# Digital_Final_-_BlackChat.net
KiCad netlist of a schematic drawn in Altium Designer
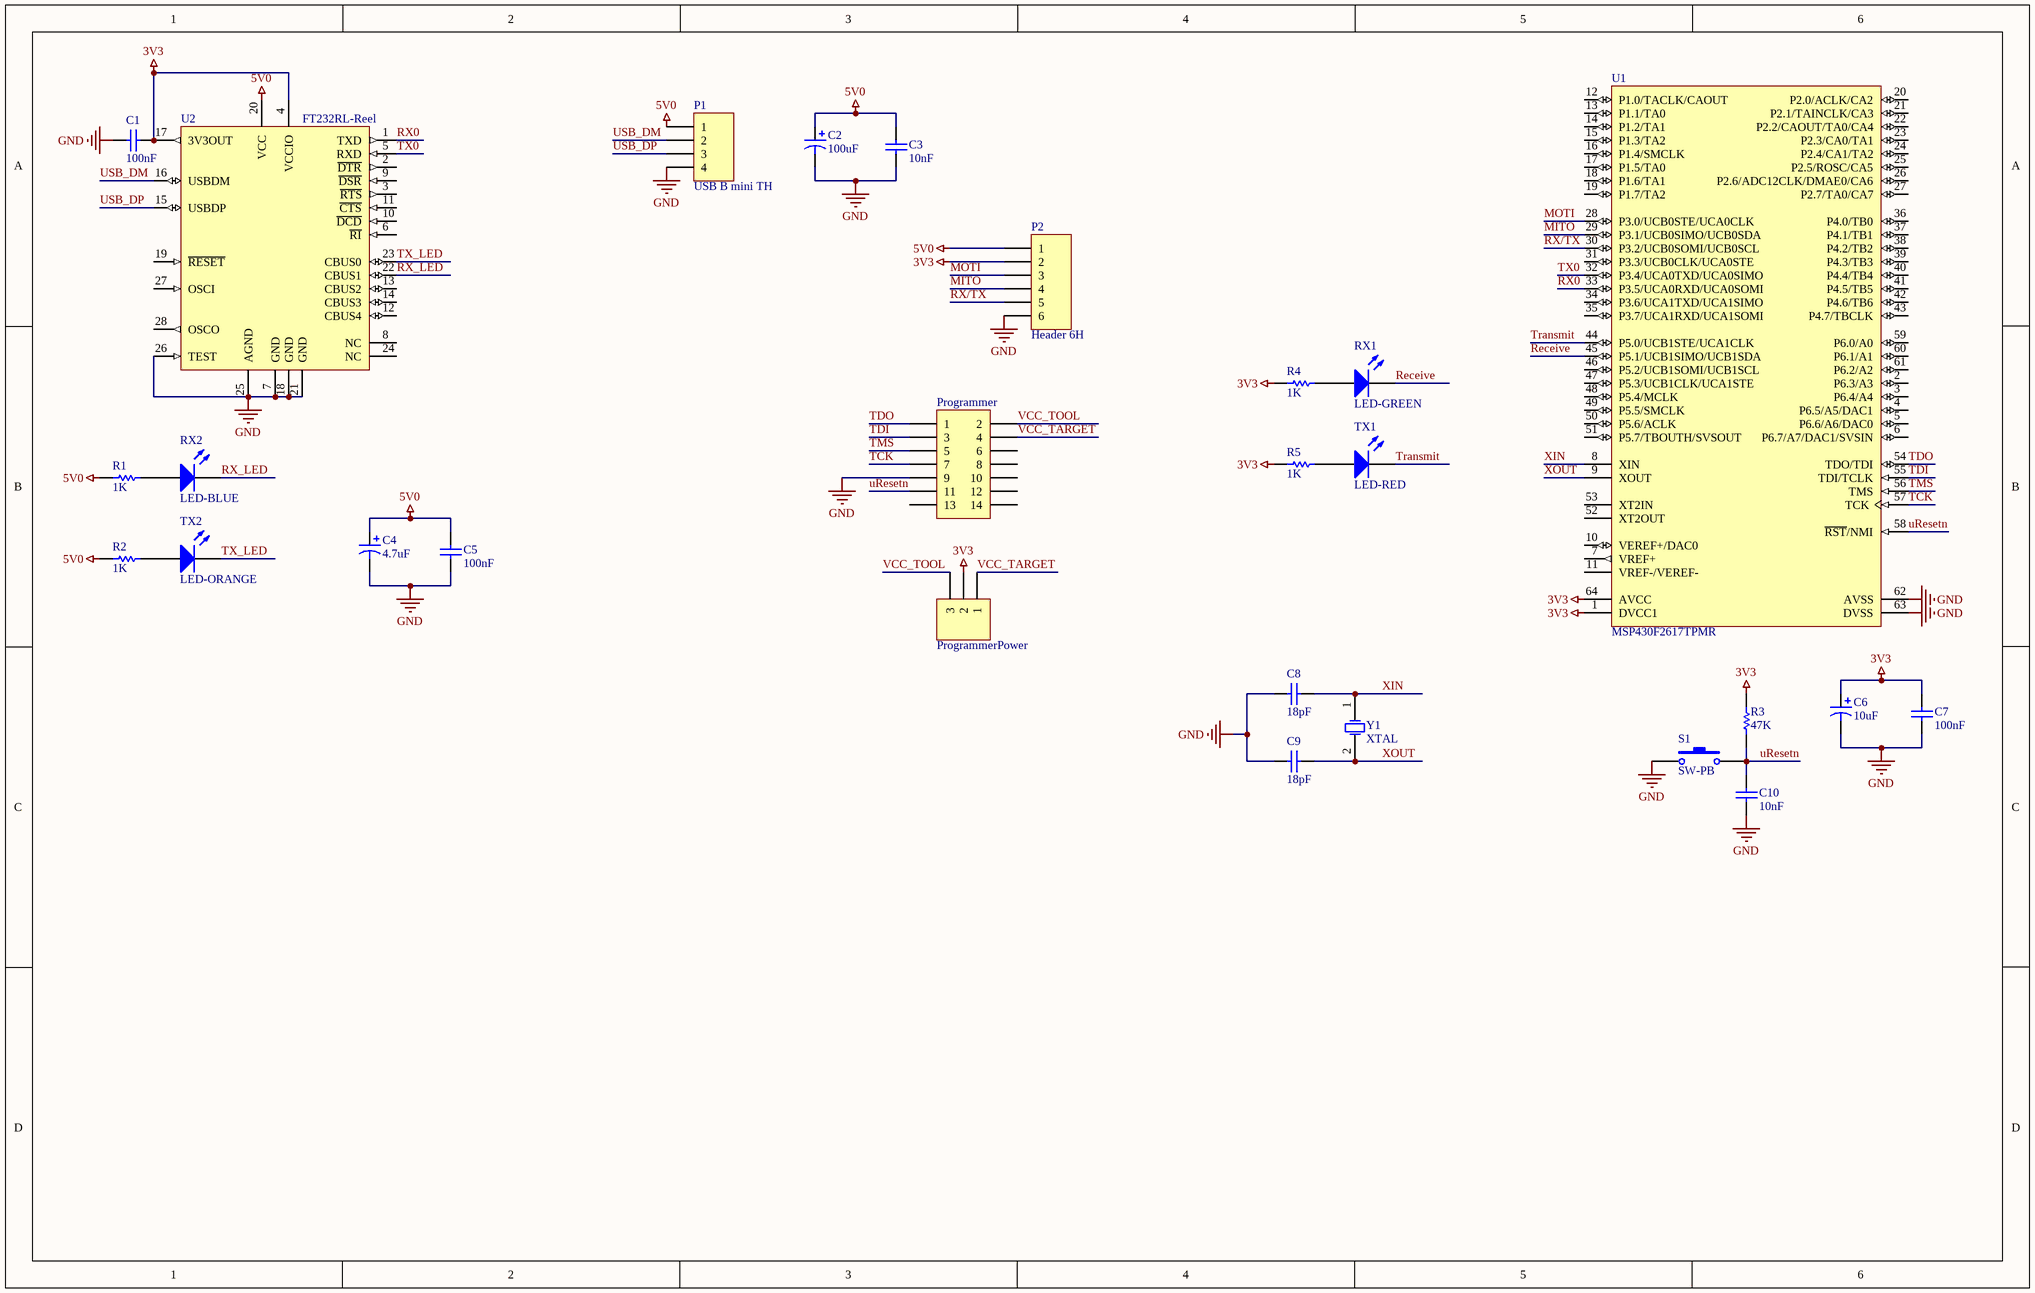
[diagram p0: Digital Final - BlackChat.SchDoc]

(export (version "E")
  (design (tool "Eeschema 10.0.6"))
  (components
    (comp (ref "C1")
      (value "100nF")
      (footprint "CAP-0805")
      (description "Capacitor")
      (fields (field (name "Comment") "Cap") (field (name "PUBLISHER") "Altium Limited"))
      (libsource (lib "Miscellaneous Devices") (part "Cap"))
    )
    (comp (ref "C2")
      (value "100uF")
      (footprint "CAP-0805")
      (description "Polarized Capacitor (Surface Mount)")
      (fields (field (name "Comment") "Cap Pol3") (field (name "PUBLISHER") "Altium Limited"))
      (libsource (lib "Miscellaneous Devices") (part "Cap Pol3"))
    )
    (comp (ref "C3")
      (value "10nF")
      (footprint "CAP-0805")
      (description "Capacitor")
      (fields (field (name "Comment") "Cap") (field (name "PUBLISHER") "Altium Limited"))
      (libsource (lib "Miscellaneous Devices") (part "Cap"))
    )
    (comp (ref "C4")
      (value "4.7uF")
      (footprint "CAP-0805")
      (description "Polarized Capacitor (Surface Mount)")
      (fields (field (name "Comment") "Cap Pol3") (field (name "PUBLISHER") "Altium Limited"))
      (libsource (lib "Miscellaneous Devices") (part "Cap Pol3"))
    )
    (comp (ref "C5")
      (value "100nF")
      (footprint "CAP-0805")
      (description "Capacitor")
      (fields (field (name "Comment") "Cap") (field (name "PUBLISHER") "Altium Limited"))
      (libsource (lib "Miscellaneous Devices") (part "Cap"))
    )
    (comp (ref "C6")
      (value "10uF")
      (footprint "CAP-0805")
      (description "Polarized Capacitor (Surface Mount)")
      (fields (field (name "Comment") "Cap Pol3") (field (name "PUBLISHER") "Altium Limited"))
      (libsource (lib "Miscellaneous Devices") (part "Cap Pol3"))
    )
    (comp (ref "C7")
      (value "100nF")
      (footprint "CAP-0805")
      (description "Capacitor")
      (fields (field (name "Comment") "Cap") (field (name "PUBLISHER") "Altium Limited"))
      (libsource (lib "Miscellaneous Devices") (part "Cap"))
    )
    (comp (ref "C8")
      (value "18pF")
      (footprint "CAP-0805")
      (description "Capacitor")
      (fields (field (name "Comment") "Cap") (field (name "PUBLISHER") "Altium Limited"))
      (libsource (lib "Miscellaneous Devices") (part "Cap"))
    )
    (comp (ref "C9")
      (value "18pF")
      (footprint "CAP-0805")
      (description "Capacitor")
      (fields (field (name "Comment") "Cap") (field (name "PUBLISHER") "Altium Limited"))
      (libsource (lib "Miscellaneous Devices") (part "Cap"))
    )
    (comp (ref "C10")
      (value "10nF")
      (footprint "CAP-0805")
      (description "Capacitor")
      (fields (field (name "Comment") "Cap") (field (name "PUBLISHER") "Altium Limited"))
      (libsource (lib "Miscellaneous Devices") (part "Cap"))
    )
    (comp (ref "P1")
      (value "USB B mini TH")
      (footprint "USB B mini Molex")
      (fields (field (name "PUBLISHER") "Altium Limited"))
      (libsource (lib "ECE Lib") (part "USB B mini TH"))
    )
    (comp (ref "P2")
      (value "Header 6H")
      (footprint "HDR1X6H")
      (description "Header, 6-Pin, Right Angle")
      (fields (field (name "PUBLISHER") "Altium Limited"))
      (libsource (lib "Miscellaneous Connectors") (part "Header 6H"))
    )
    (comp (ref "Programmer")
      (value "Header 7X2")
      (footprint "HDR2X7")
      (description "Header, 7-Pin, Dual row")
      (fields (field (name "PUBLISHER") "Altium Limited"))
      (libsource (lib "Miscellaneous Connectors") (part "Header 7X2"))
    )
    (comp (ref "ProgrammerPower")
      (value "Header 3")
      (footprint "HDR1X3")
      (description "Header, 3-Pin")
      (fields (field (name "PUBLISHER") "Altium Limited"))
      (libsource (lib "Miscellaneous Connectors") (part "Header 3"))
    )
    (comp (ref "R1")
      (value "1K")
      (footprint "RES-0805")
      (description "Resistor")
      (fields (field (name "Comment") "Res1") (field (name "PUBLISHER") "Altium Limited"))
      (libsource (lib "Miscellaneous Devices") (part "Res1"))
    )
    (comp (ref "R2")
      (value "1K")
      (footprint "RES-0805")
      (description "Resistor")
      (fields (field (name "Comment") "Res1") (field (name "PUBLISHER") "Altium Limited"))
      (libsource (lib "Miscellaneous Devices") (part "Res1"))
    )
    (comp (ref "R3")
      (value "47K")
      (footprint "RES-0805")
      (description "Resistor")
      (fields (field (name "Comment") "Res1") (field (name "PUBLISHER") "Altium Limited"))
      (libsource (lib "Miscellaneous Devices") (part "Res1"))
    )
    (comp (ref "R4")
      (value "1K")
      (footprint "RES-0805")
      (description "Resistor")
      (fields (field (name "Comment") "Res1") (field (name "PUBLISHER") "Altium Limited"))
      (libsource (lib "Miscellaneous Devices") (part "Res1"))
    )
    (comp (ref "R5")
      (value "1K")
      (footprint "RES-0805")
      (description "Resistor")
      (fields (field (name "Comment") "Res1") (field (name "PUBLISHER") "Altium Limited"))
      (libsource (lib "Miscellaneous Devices") (part "Res1"))
    )
    (comp (ref "RX1")
      (value "LED-GREEN")
      (footprint "LED-0805")
      (description "Light Emitting Diode")
      (libsource (lib "BlackChat Library") (part "LED-GENERIC"))
    )
    (comp (ref "RX2")
      (value "LED-BLUE")
      (footprint "LED-0805")
      (description "Light Emitting Diode")
      (libsource (lib "BlackChat Library") (part "LED-GENERIC"))
    )
    (comp (ref "S1")
      (value "SW-PB")
      (footprint "SW PB")
      (description "DIGIKEY SW400-ND")
      (fields (field (name "PUBLISHER") "Altium Limited"))
      (libsource (lib "ECE Lib") (part "SW-PB"))
    )
    (comp (ref "TX1")
      (value "LED-RED")
      (footprint "LED-0805")
      (description "Light Emitting Diode")
      (libsource (lib "BlackChat Library") (part "LED-GENERIC"))
    )
    (comp (ref "TX2")
      (value "LED-ORANGE")
      (footprint "LED-0805")
      (description "Light Emitting Diode")
      (libsource (lib "BlackChat Library") (part "LED-GENERIC"))
    )
    (comp (ref "U1")
      (value "MSP430F2617TPMR")
      (footprint "TI-PM64_N")
      (fields (field (name "MANUFACTURER") "Texas Instruments"))
      (libsource (lib "TI Microcontroller MSP430 16-bit Ultra-Low Power") (part "MSP430F2617TPMR"))
    )
    (comp (ref "U2")
      (value "FT232RL-Reel")
      (footprint "SSOP-28_N")
      (description "USB UART Asynchronous Serial Data Transfer Chip, SSOP-28, Tape and Reel")
      (fields (field (name "PUBLISHER") "Altium Limited"))
      (libsource (lib "BlackChat Library") (part "FT232RL-Reel"))
    )
    (comp (ref "Y1")
      (value "XTAL")
      (footprint "R38")
      (description "Crystal Oscillator")
      (fields (field (name "PUBLISHER") "Altium Limited"))
      (libsource (lib "Miscellaneous Devices") (part "XTAL"))
    )
  )
  (nets
    (net (code "1") (name "/MITO") (class "Default")
      (node (ref "P2") (pin "4") (pinfunction "4_4") (pintype "passive"))
      (node (ref "U1") (pin "29") (pinfunction "P3.1/UCB0SIMO/UCB0SDA_29") (pintype "bidirectional"))
    )
    (net (code "2") (name "/MOTI") (class "Default")
      (node (ref "P2") (pin "3") (pinfunction "3_3") (pintype "passive"))
      (node (ref "U1") (pin "28") (pinfunction "P3.0/UCB0STE/UCA0CLK_28") (pintype "bidirectional"))
    )
    (net (code "3") (name "/RX0") (class "Default")
      (node (ref "U1") (pin "33") (pinfunction "P3.5/UCA0RXD/UCA0SOMI_33") (pintype "bidirectional"))
      (node (ref "U2") (pin "1") (pinfunction "TXD_1") (pintype "output"))
    )
    (net (code "4") (name "/RX_LED") (class "Default")
      (node (ref "RX2") (pin "2") (pinfunction "K_2") (pintype "passive"))
      (node (ref "U2") (pin "22") (pinfunction "CBUS1_22") (pintype "bidirectional"))
    )
    (net (code "5") (name "/RX{slash}~{TX}") (class "Default")
      (node (ref "P2") (pin "5") (pinfunction "5_5") (pintype "passive"))
      (node (ref "U1") (pin "30") (pinfunction "P3.2/UCB0SOMI/UCB0SCL_30") (pintype "bidirectional"))
    )
    (net (code "6") (name "/Receive") (class "Default")
      (node (ref "RX1") (pin "2") (pinfunction "K_2") (pintype "passive"))
      (node (ref "U1") (pin "45") (pinfunction "P5.1/UCB1SIMO/UCB1SDA_45") (pintype "bidirectional"))
    )
    (net (code "7") (name "/TCK") (class "Default")
      (node (ref "Programmer") (pin "7") (pinfunction "7_7") (pintype "passive"))
      (node (ref "U1") (pin "57") (pinfunction "TCK_57") (pintype "input"))
    )
    (net (code "8") (name "/TDI") (class "Default")
      (node (ref "Programmer") (pin "3") (pinfunction "3_3") (pintype "passive"))
      (node (ref "U1") (pin "55") (pinfunction "TDI/TCLK_55") (pintype "input"))
    )
    (net (code "9") (name "/TDO") (class "Default")
      (node (ref "Programmer") (pin "1") (pinfunction "1_1") (pintype "passive"))
      (node (ref "U1") (pin "54") (pinfunction "TDO/TDI_54") (pintype "bidirectional"))
    )
    (net (code "10") (name "/TMS") (class "Default")
      (node (ref "Programmer") (pin "5") (pinfunction "5_5") (pintype "passive"))
      (node (ref "U1") (pin "56") (pinfunction "TMS_56") (pintype "input"))
    )
    (net (code "11") (name "/TX0") (class "Default")
      (node (ref "U1") (pin "32") (pinfunction "P3.4/UCA0TXD/UCA0SIMO_32") (pintype "bidirectional"))
      (node (ref "U2") (pin "5") (pinfunction "RXD_5") (pintype "input"))
    )
    (net (code "12") (name "/TX_LED") (class "Default")
      (node (ref "TX2") (pin "2") (pinfunction "K_2") (pintype "passive"))
      (node (ref "U2") (pin "23") (pinfunction "CBUS0_23") (pintype "bidirectional"))
    )
    (net (code "13") (name "/Transmit") (class "Default")
      (node (ref "TX1") (pin "2") (pinfunction "K_2") (pintype "passive"))
      (node (ref "U1") (pin "44") (pinfunction "P5.0/UCB1STE/UCA1CLK_44") (pintype "bidirectional"))
    )
    (net (code "14") (name "/USB_DM") (class "Default")
      (node (ref "P1") (pin "2") (pinfunction "2_2") (pintype "passive"))
      (node (ref "U2") (pin "16") (pinfunction "USBDM_16") (pintype "bidirectional"))
    )
    (net (code "15") (name "/USB_DP") (class "Default")
      (node (ref "P1") (pin "3") (pinfunction "3_3") (pintype "passive"))
      (node (ref "U2") (pin "15") (pinfunction "USBDP_15") (pintype "bidirectional"))
    )
    (net (code "16") (name "/VCC_TARGET") (class "Default")
      (node (ref "Programmer") (pin "4") (pinfunction "4_4") (pintype "passive"))
      (node (ref "ProgrammerPower") (pin "1") (pinfunction "1_1") (pintype "passive"))
    )
    (net (code "17") (name "/VCC_TOOL") (class "Default")
      (node (ref "Programmer") (pin "2") (pinfunction "2_2") (pintype "passive"))
      (node (ref "ProgrammerPower") (pin "3") (pinfunction "3_3") (pintype "passive"))
    )
    (net (code "18") (name "/XIN") (class "Default")
      (node (ref "C8") (pin "1") (pinfunction "1_1") (pintype "passive"))
      (node (ref "U1") (pin "8") (pinfunction "XIN_8") (pintype "passive"))
      (node (ref "Y1") (pin "1") (pinfunction "OSC1_1") (pintype "passive"))
    )
    (net (code "19") (name "/XOUT") (class "Default")
      (node (ref "C9") (pin "1") (pinfunction "1_1") (pintype "passive"))
      (node (ref "U1") (pin "9") (pinfunction "XOUT_9") (pintype "passive"))
      (node (ref "Y1") (pin "2") (pinfunction "OSC2_2") (pintype "passive"))
    )
    (net (code "20") (name "/uResetn") (class "Default")
      (node (ref "C10") (pin "2") (pinfunction "2_2") (pintype "passive"))
      (node (ref "Programmer") (pin "11") (pinfunction "11_11") (pintype "passive"))
      (node (ref "R3") (pin "1") (pinfunction "1_1") (pintype "passive"))
      (node (ref "S1") (pin "2") (pinfunction "2_2") (pintype "passive"))
      (node (ref "U1") (pin "58") (pinfunction "~{RST}/NMI_58") (pintype "input"))
    )
    (net (code "21") (name "3V3") (class "Default")
      (node (ref "C1") (pin "1") (pinfunction "1_1") (pintype "passive"))
      (node (ref "C6") (pin "1") (pinfunction "1_1") (pintype "passive"))
      (node (ref "C7") (pin "2") (pinfunction "2_2") (pintype "passive"))
      (node (ref "P2") (pin "2") (pinfunction "2_2") (pintype "passive"))
      (node (ref "ProgrammerPower") (pin "2") (pinfunction "2_2") (pintype "passive"))
      (node (ref "R3") (pin "2") (pinfunction "2_2") (pintype "passive"))
      (node (ref "R4") (pin "2") (pinfunction "2_2") (pintype "passive"))
      (node (ref "R5") (pin "2") (pinfunction "2_2") (pintype "passive"))
      (node (ref "U1") (pin "1") (pinfunction "DVCC1_1") (pintype "power_in"))
      (node (ref "U1") (pin "64") (pinfunction "AVCC_64") (pintype "power_in"))
      (node (ref "U2") (pin "17") (pinfunction "3V3OUT_17") (pintype "output"))
      (node (ref "U2") (pin "4") (pinfunction "VCCIO_4") (pintype "power_in"))
    )
    (net (code "22") (name "5V0") (class "Default")
      (node (ref "C2") (pin "1") (pinfunction "1_1") (pintype "passive"))
      (node (ref "C3") (pin "2") (pinfunction "2_2") (pintype "passive"))
      (node (ref "C4") (pin "1") (pinfunction "1_1") (pintype "passive"))
      (node (ref "C5") (pin "2") (pinfunction "2_2") (pintype "passive"))
      (node (ref "P1") (pin "1") (pinfunction "1_1") (pintype "passive"))
      (node (ref "P2") (pin "1") (pinfunction "1_1") (pintype "passive"))
      (node (ref "R1") (pin "2") (pinfunction "2_2") (pintype "passive"))
      (node (ref "R2") (pin "2") (pinfunction "2_2") (pintype "passive"))
      (node (ref "U2") (pin "20") (pinfunction "VCC_20") (pintype "power_in"))
    )
    (net (code "23") (name "GND") (class "Default")
      (node (ref "C1") (pin "2") (pinfunction "2_2") (pintype "passive"))
      (node (ref "C10") (pin "1") (pinfunction "1_1") (pintype "passive"))
      (node (ref "C2") (pin "2") (pinfunction "2_2") (pintype "passive"))
      (node (ref "C3") (pin "1") (pinfunction "1_1") (pintype "passive"))
      (node (ref "C4") (pin "2") (pinfunction "2_2") (pintype "passive"))
      (node (ref "C5") (pin "1") (pinfunction "1_1") (pintype "passive"))
      (node (ref "C6") (pin "2") (pinfunction "2_2") (pintype "passive"))
      (node (ref "C7") (pin "1") (pinfunction "1_1") (pintype "passive"))
      (node (ref "C8") (pin "2") (pinfunction "2_2") (pintype "passive"))
      (node (ref "C9") (pin "2") (pinfunction "2_2") (pintype "passive"))
      (node (ref "P1") (pin "4") (pinfunction "4_4") (pintype "passive"))
      (node (ref "P2") (pin "6") (pinfunction "6_6") (pintype "passive"))
      (node (ref "Programmer") (pin "9") (pinfunction "9_9") (pintype "passive"))
      (node (ref "S1") (pin "1") (pinfunction "1_1") (pintype "passive"))
      (node (ref "U1") (pin "62") (pinfunction "AVSS_62") (pintype "power_in"))
      (node (ref "U1") (pin "63") (pinfunction "DVSS_63") (pintype "power_in"))
      (node (ref "U2") (pin "18") (pinfunction "GND_18") (pintype "power_in"))
      (node (ref "U2") (pin "21") (pinfunction "GND_21") (pintype "power_in"))
      (node (ref "U2") (pin "25") (pinfunction "AGND_25") (pintype "power_in"))
      (node (ref "U2") (pin "26") (pinfunction "TEST_26") (pintype "input"))
      (node (ref "U2") (pin "7") (pinfunction "GND_7") (pintype "power_in"))
    )
    (net (code "24") (name "Net-(RX1-A)") (class "Default")
      (node (ref "R4") (pin "1") (pinfunction "1_1") (pintype "passive"))
      (node (ref "RX1") (pin "1") (pinfunction "A_1") (pintype "passive"))
    )
    (net (code "25") (name "Net-(RX2-A)") (class "Default")
      (node (ref "R1") (pin "1") (pinfunction "1_1") (pintype "passive"))
      (node (ref "RX2") (pin "1") (pinfunction "A_1") (pintype "passive"))
    )
    (net (code "26") (name "Net-(TX1-A)") (class "Default")
      (node (ref "R5") (pin "1") (pinfunction "1_1") (pintype "passive"))
      (node (ref "TX1") (pin "1") (pinfunction "A_1") (pintype "passive"))
    )
    (net (code "27") (name "Net-(TX2-A)") (class "Default")
      (node (ref "R2") (pin "1") (pinfunction "1_1") (pintype "passive"))
      (node (ref "TX2") (pin "1") (pinfunction "A_1") (pintype "passive"))
    )
    (net (code "28") (name "unconnected-(Programmer-Pad6)") (class "Default")
      (node (ref "Programmer") (pin "6") (pinfunction "6_6") (pintype "passive"))
    )
    (net (code "29") (name "unconnected-(Programmer-Pad8)") (class "Default")
      (node (ref "Programmer") (pin "8") (pinfunction "8_8") (pintype "passive"))
    )
    (net (code "30") (name "unconnected-(Programmer-Pad10)") (class "Default")
      (node (ref "Programmer") (pin "10") (pinfunction "10_10") (pintype "passive"))
    )
    (net (code "31") (name "unconnected-(Programmer-Pad12)") (class "Default")
      (node (ref "Programmer") (pin "12") (pinfunction "12_12") (pintype "passive"))
    )
    (net (code "32") (name "unconnected-(Programmer-Pad13)") (class "Default")
      (node (ref "Programmer") (pin "13") (pinfunction "13_13") (pintype "passive"))
    )
    (net (code "33") (name "unconnected-(Programmer-Pad14)") (class "Default")
      (node (ref "Programmer") (pin "14") (pinfunction "14_14") (pintype "passive"))
    )
    (net (code "34") (name "unconnected-(U1-P1.0{slash}TACLK{slash}CAOUT-Pad12)") (class "Default")
      (node (ref "U1") (pin "12") (pinfunction "P1.0/TACLK/CAOUT_12") (pintype "bidirectional"))
    )
    (net (code "35") (name "unconnected-(U1-P1.1{slash}TA0-Pad13)") (class "Default")
      (node (ref "U1") (pin "13") (pinfunction "P1.1/TA0_13") (pintype "bidirectional"))
    )
    (net (code "36") (name "unconnected-(U1-P1.2{slash}TA1-Pad14)") (class "Default")
      (node (ref "U1") (pin "14") (pinfunction "P1.2/TA1_14") (pintype "bidirectional"))
    )
    (net (code "37") (name "unconnected-(U1-P1.3{slash}TA2-Pad15)") (class "Default")
      (node (ref "U1") (pin "15") (pinfunction "P1.3/TA2_15") (pintype "bidirectional"))
    )
    (net (code "38") (name "unconnected-(U1-P1.4{slash}SMCLK-Pad16)") (class "Default")
      (node (ref "U1") (pin "16") (pinfunction "P1.4/SMCLK_16") (pintype "bidirectional"))
    )
    (net (code "39") (name "unconnected-(U1-P1.5{slash}TA0-Pad17)") (class "Default")
      (node (ref "U1") (pin "17") (pinfunction "P1.5/TA0_17") (pintype "bidirectional"))
    )
    (net (code "40") (name "unconnected-(U1-P1.6{slash}TA1-Pad18)") (class "Default")
      (node (ref "U1") (pin "18") (pinfunction "P1.6/TA1_18") (pintype "bidirectional"))
    )
    (net (code "41") (name "unconnected-(U1-P1.7{slash}TA2-Pad19)") (class "Default")
      (node (ref "U1") (pin "19") (pinfunction "P1.7/TA2_19") (pintype "bidirectional"))
    )
    (net (code "42") (name "unconnected-(U1-P2.0{slash}ACLK{slash}CA2-Pad20)") (class "Default")
      (node (ref "U1") (pin "20") (pinfunction "P2.0/ACLK/CA2_20") (pintype "bidirectional"))
    )
    (net (code "43") (name "unconnected-(U1-P2.1{slash}TAINCLK{slash}CA3-Pad21)") (class "Default")
      (node (ref "U1") (pin "21") (pinfunction "P2.1/TAINCLK/CA3_21") (pintype "bidirectional"))
    )
    (net (code "44") (name "unconnected-(U1-P2.2{slash}CAOUT{slash}TA0{slash}CA4-Pad22)") (class "Default")
      (node (ref "U1") (pin "22") (pinfunction "P2.2/CAOUT/TA0/CA4_22") (pintype "bidirectional"))
    )
    (net (code "45") (name "unconnected-(U1-P2.3{slash}CA0{slash}TA1-Pad23)") (class "Default")
      (node (ref "U1") (pin "23") (pinfunction "P2.3/CA0/TA1_23") (pintype "bidirectional"))
    )
    (net (code "46") (name "unconnected-(U1-P2.4{slash}CA1{slash}TA2-Pad24)") (class "Default")
      (node (ref "U1") (pin "24") (pinfunction "P2.4/CA1/TA2_24") (pintype "bidirectional"))
    )
    (net (code "47") (name "unconnected-(U1-P2.5{slash}ROSC{slash}CA5-Pad25)") (class "Default")
      (node (ref "U1") (pin "25") (pinfunction "P2.5/ROSC/CA5_25") (pintype "bidirectional"))
    )
    (net (code "48") (name "unconnected-(U1-P2.6{slash}ADC12CLK{slash}DMAE0{slash}CA6-Pad26)") (class "Default")
      (node (ref "U1") (pin "26") (pinfunction "P2.6/ADC12CLK/DMAE0/CA6_26") (pintype "bidirectional"))
    )
    (net (code "49") (name "unconnected-(U1-P2.7{slash}TA0{slash}CA7-Pad27)") (class "Default")
      (node (ref "U1") (pin "27") (pinfunction "P2.7/TA0/CA7_27") (pintype "bidirectional"))
    )
    (net (code "50") (name "unconnected-(U1-P3.3{slash}UCB0CLK{slash}UCA0STE-Pad31)") (class "Default")
      (node (ref "U1") (pin "31") (pinfunction "P3.3/UCB0CLK/UCA0STE_31") (pintype "bidirectional"))
    )
    (net (code "51") (name "unconnected-(U1-P3.6{slash}UCA1TXD{slash}UCA1SIMO-Pad34)") (class "Default")
      (node (ref "U1") (pin "34") (pinfunction "P3.6/UCA1TXD/UCA1SIMO_34") (pintype "bidirectional"))
    )
    (net (code "52") (name "unconnected-(U1-P3.7{slash}UCA1RXD{slash}UCA1SOMI-Pad35)") (class "Default")
      (node (ref "U1") (pin "35") (pinfunction "P3.7/UCA1RXD/UCA1SOMI_35") (pintype "bidirectional"))
    )
    (net (code "53") (name "unconnected-(U1-P4.0{slash}TB0-Pad36)") (class "Default")
      (node (ref "U1") (pin "36") (pinfunction "P4.0/TB0_36") (pintype "bidirectional"))
    )
    (net (code "54") (name "unconnected-(U1-P4.1{slash}TB1-Pad37)") (class "Default")
      (node (ref "U1") (pin "37") (pinfunction "P4.1/TB1_37") (pintype "bidirectional"))
    )
    (net (code "55") (name "unconnected-(U1-P4.2{slash}TB2-Pad38)") (class "Default")
      (node (ref "U1") (pin "38") (pinfunction "P4.2/TB2_38") (pintype "bidirectional"))
    )
    (net (code "56") (name "unconnected-(U1-P4.3{slash}TB3-Pad39)") (class "Default")
      (node (ref "U1") (pin "39") (pinfunction "P4.3/TB3_39") (pintype "bidirectional"))
    )
    (net (code "57") (name "unconnected-(U1-P4.4{slash}TB4-Pad40)") (class "Default")
      (node (ref "U1") (pin "40") (pinfunction "P4.4/TB4_40") (pintype "bidirectional"))
    )
    (net (code "58") (name "unconnected-(U1-P4.5{slash}TB5-Pad41)") (class "Default")
      (node (ref "U1") (pin "41") (pinfunction "P4.5/TB5_41") (pintype "bidirectional"))
    )
    (net (code "59") (name "unconnected-(U1-P4.6{slash}TB6-Pad42)") (class "Default")
      (node (ref "U1") (pin "42") (pinfunction "P4.6/TB6_42") (pintype "bidirectional"))
    )
    (net (code "60") (name "unconnected-(U1-P4.7{slash}TBCLK-Pad43)") (class "Default")
      (node (ref "U1") (pin "43") (pinfunction "P4.7/TBCLK_43") (pintype "bidirectional"))
    )
    (net (code "61") (name "unconnected-(U1-P5.2{slash}UCB1SOMI{slash}UCB1SCL-Pad46)") (class "Default")
      (node (ref "U1") (pin "46") (pinfunction "P5.2/UCB1SOMI/UCB1SCL_46") (pintype "bidirectional"))
    )
    (net (code "62") (name "unconnected-(U1-P5.3{slash}UCB1CLK{slash}UCA1STE-Pad47)") (class "Default")
      (node (ref "U1") (pin "47") (pinfunction "P5.3/UCB1CLK/UCA1STE_47") (pintype "bidirectional"))
    )
    (net (code "63") (name "unconnected-(U1-P5.4{slash}MCLK-Pad48)") (class "Default")
      (node (ref "U1") (pin "48") (pinfunction "P5.4/MCLK_48") (pintype "bidirectional"))
    )
    (net (code "64") (name "unconnected-(U1-P5.5{slash}SMCLK-Pad49)") (class "Default")
      (node (ref "U1") (pin "49") (pinfunction "P5.5/SMCLK_49") (pintype "bidirectional"))
    )
    (net (code "65") (name "unconnected-(U1-P5.6{slash}ACLK-Pad50)") (class "Default")
      (node (ref "U1") (pin "50") (pinfunction "P5.6/ACLK_50") (pintype "bidirectional"))
    )
    (net (code "66") (name "unconnected-(U1-P5.7{slash}TBOUTH{slash}SVSOUT-Pad51)") (class "Default")
      (node (ref "U1") (pin "51") (pinfunction "P5.7/TBOUTH/SVSOUT_51") (pintype "bidirectional"))
    )
    (net (code "67") (name "unconnected-(U1-P6.0{slash}A0-Pad59)") (class "Default")
      (node (ref "U1") (pin "59") (pinfunction "P6.0/A0_59") (pintype "bidirectional"))
    )
    (net (code "68") (name "unconnected-(U1-P6.1{slash}A1-Pad60)") (class "Default")
      (node (ref "U1") (pin "60") (pinfunction "P6.1/A1_60") (pintype "bidirectional"))
    )
    (net (code "69") (name "unconnected-(U1-P6.2{slash}A2-Pad61)") (class "Default")
      (node (ref "U1") (pin "61") (pinfunction "P6.2/A2_61") (pintype "bidirectional"))
    )
    (net (code "70") (name "unconnected-(U1-P6.3{slash}A3-Pad2)") (class "Default")
      (node (ref "U1") (pin "2") (pinfunction "P6.3/A3_2") (pintype "bidirectional"))
    )
    (net (code "71") (name "unconnected-(U1-P6.4{slash}A4-Pad3)") (class "Default")
      (node (ref "U1") (pin "3") (pinfunction "P6.4/A4_3") (pintype "bidirectional"))
    )
    (net (code "72") (name "unconnected-(U1-P6.5{slash}A5{slash}DAC1-Pad4)") (class "Default")
      (node (ref "U1") (pin "4") (pinfunction "P6.5/A5/DAC1_4") (pintype "bidirectional"))
    )
    (net (code "73") (name "unconnected-(U1-P6.6{slash}A6{slash}DAC0-Pad5)") (class "Default")
      (node (ref "U1") (pin "5") (pinfunction "P6.6/A6/DAC0_5") (pintype "bidirectional"))
    )
    (net (code "74") (name "unconnected-(U1-P6.7{slash}A7{slash}DAC1{slash}SVSIN-Pad6)") (class "Default")
      (node (ref "U1") (pin "6") (pinfunction "P6.7/A7/DAC1/SVSIN_6") (pintype "bidirectional"))
    )
    (net (code "75") (name "unconnected-(U1-VEREF+{slash}DAC0-Pad10)") (class "Default")
      (node (ref "U1") (pin "10") (pinfunction "VEREF+/DAC0_10") (pintype "bidirectional"))
    )
    (net (code "76") (name "unconnected-(U1-VREF+-Pad7)") (class "Default")
      (node (ref "U1") (pin "7") (pinfunction "VREF+_7") (pintype "output"))
    )
    (net (code "77") (name "unconnected-(U1-VREF-{slash}VEREF--Pad11)") (class "Default")
      (node (ref "U1") (pin "11") (pinfunction "VREF-/VEREF-_11") (pintype "passive"))
    )
    (net (code "78") (name "unconnected-(U1-XT2IN-Pad53)") (class "Default")
      (node (ref "U1") (pin "53") (pinfunction "XT2IN_53") (pintype "passive"))
    )
    (net (code "79") (name "unconnected-(U1-XT2OUT-Pad52)") (class "Default")
      (node (ref "U1") (pin "52") (pinfunction "XT2OUT_52") (pintype "passive"))
    )
    (net (code "80") (name "unconnected-(U2-CBUS2-Pad13)") (class "Default")
      (node (ref "U2") (pin "13") (pinfunction "CBUS2_13") (pintype "bidirectional"))
    )
    (net (code "81") (name "unconnected-(U2-CBUS3-Pad14)") (class "Default")
      (node (ref "U2") (pin "14") (pinfunction "CBUS3_14") (pintype "bidirectional"))
    )
    (net (code "82") (name "unconnected-(U2-CBUS4-Pad12)") (class "Default")
      (node (ref "U2") (pin "12") (pinfunction "CBUS4_12") (pintype "bidirectional"))
    )
    (net (code "83") (name "unconnected-(U2-NC-Pad8)") (class "Default")
      (node (ref "U2") (pin "8") (pinfunction "NC_8") (pintype "passive"))
    )
    (net (code "84") (name "unconnected-(U2-NC-Pad24)") (class "Default")
      (node (ref "U2") (pin "24") (pinfunction "NC_24") (pintype "passive"))
    )
    (net (code "85") (name "unconnected-(U2-OSCI-Pad27)") (class "Default")
      (node (ref "U2") (pin "27") (pinfunction "OSCI_27") (pintype "input"))
    )
    (net (code "86") (name "unconnected-(U2-OSCO-Pad28)") (class "Default")
      (node (ref "U2") (pin "28") (pinfunction "OSCO_28") (pintype "output"))
    )
    (net (code "87") (name "unconnected-(U2-~{CTS}-Pad11)") (class "Default")
      (node (ref "U2") (pin "11") (pinfunction "~{CTS}_11") (pintype "input"))
    )
    (net (code "88") (name "unconnected-(U2-~{DCD}-Pad10)") (class "Default")
      (node (ref "U2") (pin "10") (pinfunction "~{DCD}_10") (pintype "input"))
    )
    (net (code "89") (name "unconnected-(U2-~{DSR}-Pad9)") (class "Default")
      (node (ref "U2") (pin "9") (pinfunction "~{DSR}_9") (pintype "input"))
    )
    (net (code "90") (name "unconnected-(U2-~{DTR}-Pad2)") (class "Default")
      (node (ref "U2") (pin "2") (pinfunction "~{DTR}_2") (pintype "output"))
    )
    (net (code "91") (name "unconnected-(U2-~{RESET}-Pad19)") (class "Default")
      (node (ref "U2") (pin "19") (pinfunction "~{RESET}_19") (pintype "input"))
    )
    (net (code "92") (name "unconnected-(U2-~{RI}-Pad6)") (class "Default")
      (node (ref "U2") (pin "6") (pinfunction "~{RI}_6") (pintype "input"))
    )
    (net (code "93") (name "unconnected-(U2-~{RTS}-Pad3)") (class "Default")
      (node (ref "U2") (pin "3") (pinfunction "~{RTS}_3") (pintype "output"))
    )
  )
)
